# A4a_ESP32-WROOM-32.net
KiCad netlist of a schematic drawn in EAGLE
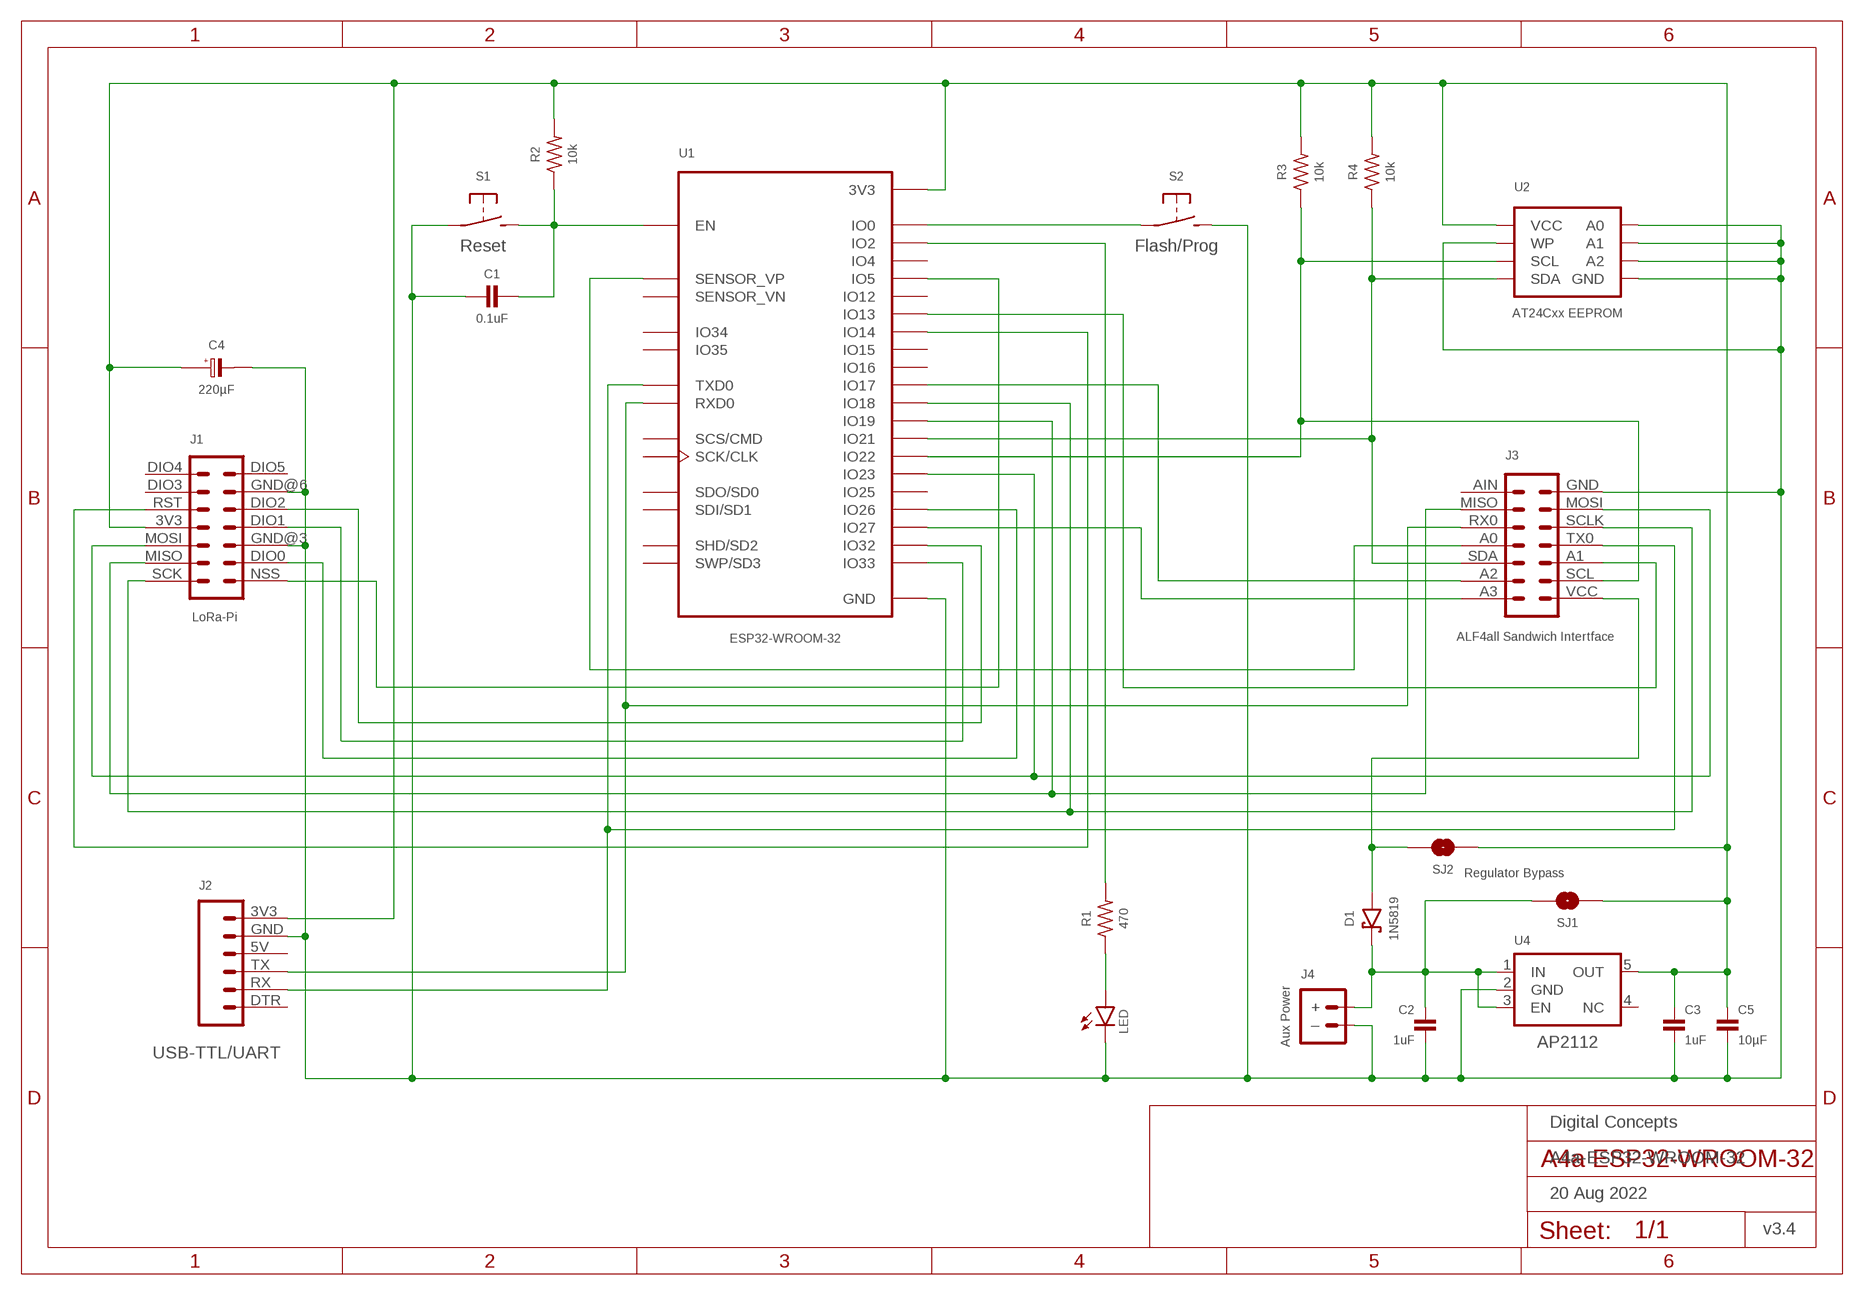
[diagram p0: schematic, sheet 1]

(export (version "E")
  (design (tool "Eeschema 10.0.6"))
  (components
    (comp (ref "C1")
      (value "0.1uF")
      (footprint "eagle-import:C0805@1")
      (libsource (lib "eagle-import") (part "CAPACITOR"))
    )
    (comp (ref "C2")
      (value "1uF")
      (footprint "eagle-import:C0805")
      (libsource (lib "eagle-import") (part "CAPACITOR-0805"))
    )
    (comp (ref "C3")
      (value "1uF")
      (footprint "eagle-import:C0805")
      (libsource (lib "eagle-import") (part "CAPACITOR-0805"))
    )
    (comp (ref "C4")
      (value "220µF")
      (footprint "eagle-import:C3528-21")
      (libsource (lib "eagle-import") (part "CAPACITOR-TANTALUM-3528"))
    )
    (comp (ref "C5")
      (value "10µF")
      (footprint "eagle-import:C0805")
      (libsource (lib "eagle-import") (part "CAPACITOR-0805"))
    )
    (comp (ref "D1")
      (value "1N5819")
      (footprint "eagle-import:SOD-123")
      (libsource (lib "eagle-import") (part "DIODE-SCHOTTKY-1N5819"))
    )
    (comp (ref "J1")
      (value "LoRa-Pi")
      (footprint "eagle-import:RFM95W-PI")
      (libsource (lib "eagle-import") (part "RFM95W-PI-HEADER"))
    )
    (comp (ref "J2")
      (value "USB-TTL/UART")
      (footprint "eagle-import:CONN_06-UART")
      (libsource (lib "eagle-import") (part "HEADER-1X6-UART"))
    )
    (comp (ref "J3")
      (value "ALF4all Sandwich Intertface")
      (footprint "eagle-import:CONN_2X7-ALF4ALL-PROCESSOR-B")
      (libsource (lib "eagle-import") (part "HEADER-2X7-ALF4ALL-PROCESSOR-B"))
    )
    (comp (ref "J4")
      (value "Aux Power")
      (footprint "eagle-import:JST-PH2.0-2-HORIZONTAL")
      (libsource (lib "eagle-import") (part "JST-PH2.0-2-MALE-HORIZONTALJST-PTH-2"))
    )
    (comp (ref "LED")
      (value "LEDCHIP-LED0805")
      (footprint "eagle-import:CHIP-LED0805")
      (libsource (lib "eagle-import") (part "LEDCHIP-LED0805"))
    )
    (comp (ref "R1")
      (value "470")
      (footprint "eagle-import:R0805")
      (libsource (lib "eagle-import") (part "RESISTORR0805"))
    )
    (comp (ref "R2")
      (value "10k")
      (footprint "eagle-import:R0805")
      (libsource (lib "eagle-import") (part "RESISTORR0805"))
    )
    (comp (ref "R3")
      (value "10k")
      (footprint "eagle-import:R0805")
      (libsource (lib "eagle-import") (part "RESISTORR0805"))
    )
    (comp (ref "R4")
      (value "10k")
      (footprint "eagle-import:R0805")
      (libsource (lib "eagle-import") (part "RESISTORR0805"))
    )
    (comp (ref "S1")
      (value "Reset")
      (footprint "eagle-import:SWITCH-2-PAD")
      (libsource (lib "eagle-import") (part "SWITCH-MOMENTARY-2-PIN"))
    )
    (comp (ref "S2")
      (value "Flash/Prog")
      (footprint "eagle-import:SWITCH-2-PAD")
      (libsource (lib "eagle-import") (part "SWITCH-MOMENTARY-2-PIN"))
    )
    (comp (ref "SJ1")
      (value "Regulator Bypass")
      (footprint "eagle-import:SJ")
      (libsource (lib "eagle-import") (part "SJ"))
    )
    (comp (ref "SJ2") (value "SJ") (footprint "eagle-import:SJ") (libsource (lib "eagle-import") (part "SJ")))
    (comp (ref "U1")
      (value "ESP32-WROOM-32")
      (footprint "eagle-import:ESP32-WROOM-32")
      (libsource (lib "eagle-import") (part "ESP32-WROOM-32"))
    )
    (comp (ref "U2")
      (value "AT24Cxx EEPROM")
      (footprint "eagle-import:SOP-8")
      (libsource (lib "eagle-import") (part "AT24CXX-EEPROM"))
    )
    (comp (ref "U4")
      (value "AP2112")
      (footprint "eagle-import:SOT25")
      (libsource (lib "eagle-import") (part "REGULATOR-AP2112"))
    )
  )
  (nets
    (net (code "1") (name "Net-(C4-+)") (class "Default")
      (node (ref "C3") (pin "1") (pinfunction "1_1") (pintype "passive"))
      (node (ref "C4") (pin "1") (pinfunction "+_1") (pintype "passive"))
      (node (ref "C5") (pin "1") (pinfunction "1_1") (pintype "passive"))
      (node (ref "J1") (pin "3V3") (pinfunction "11_3V3") (pintype "passive"))
      (node (ref "J2") (pin "3V3") (pinfunction "6_3V3") (pintype "passive"))
      (node (ref "R2") (pin "2") (pinfunction "2_2") (pintype "passive"))
      (node (ref "R3") (pin "2") (pinfunction "2_2") (pintype "passive"))
      (node (ref "R4") (pin "2") (pinfunction "2_2") (pintype "passive"))
      (node (ref "SJ1") (pin "2") (pinfunction "2_2") (pintype "passive"))
      (node (ref "SJ2") (pin "2") (pinfunction "2_2") (pintype "passive"))
      (node (ref "U1") (pin "3V3") (pinfunction "3V3_3V3") (pintype "power_in"))
      (node (ref "U2") (pin "P$8") (pinfunction "VCC_P$8") (pintype "bidirectional"))
      (node (ref "U4") (pin "5") (pinfunction "OUT_5") (pintype "power_in"))
    )
    (net (code "2") (name "Net-(C4--)") (class "Default")
      (node (ref "C1") (pin "2") (pinfunction "2_2") (pintype "passive"))
      (node (ref "C2") (pin "2") (pinfunction "2_2") (pintype "passive"))
      (node (ref "C3") (pin "2") (pinfunction "2_2") (pintype "passive"))
      (node (ref "C4") (pin "2") (pinfunction "-_2") (pintype "passive"))
      (node (ref "C5") (pin "2") (pinfunction "2_2") (pintype "passive"))
      (node (ref "J1") (pin "GND@3") (pinfunction "3_GND@3") (pintype "passive"))
      (node (ref "J1") (pin "GND@6") (pinfunction "6_GND@6") (pintype "passive"))
      (node (ref "J2") (pin "GND") (pinfunction "5_GND") (pintype "passive"))
      (node (ref "J3") (pin "GND") (pinfunction "7_GND") (pintype "passive"))
      (node (ref "J4") (pin "-") (pinfunction "–_-") (pintype "power_in"))
      (node (ref "LED") (pin "C") (pinfunction "C_C") (pintype "passive"))
      (node (ref "S1") (pin "P$1") (pinfunction "P_P$1") (pintype "passive"))
      (node (ref "S2") (pin "P$2") (pinfunction "S_P$2") (pintype "passive"))
      (node (ref "U1") (pin "GND@1") (pinfunction "GND_GND@1") (pintype "power_in"))
      (node (ref "U1") (pin "GND@15") (pinfunction "GND_GND@15") (pintype "power_in"))
      (node (ref "U1") (pin "GND@38") (pinfunction "GND_GND@38") (pintype "power_in"))
      (node (ref "U1") (pin "TP") (pinfunction "GND_TP") (pintype "power_in"))
      (node (ref "U1") (pin "TP@P1") (pinfunction "GND_TP@P1") (pintype "power_in"))
      (node (ref "U1") (pin "TP@P2") (pinfunction "GND_TP@P2") (pintype "power_in"))
      (node (ref "U1") (pin "TP@P3") (pinfunction "GND_TP@P3") (pintype "power_in"))
      (node (ref "U1") (pin "TP@P4") (pinfunction "GND_TP@P4") (pintype "power_in"))
      (node (ref "U1") (pin "TP@P5") (pinfunction "GND_TP@P5") (pintype "power_in"))
      (node (ref "U1") (pin "TP@P6") (pinfunction "GND_TP@P6") (pintype "power_in"))
      (node (ref "U1") (pin "TP@P7") (pinfunction "GND_TP@P7") (pintype "power_in"))
      (node (ref "U1") (pin "TP@P8") (pinfunction "GND_TP@P8") (pintype "power_in"))
      (node (ref "U1") (pin "TP@P9") (pinfunction "GND_TP@P9") (pintype "power_in"))
      (node (ref "U1") (pin "TP@V1") (pinfunction "GND_TP@V1") (pintype "power_in"))
      (node (ref "U1") (pin "TP@V10") (pinfunction "GND_TP@V10") (pintype "power_in"))
      (node (ref "U1") (pin "TP@V11") (pinfunction "GND_TP@V11") (pintype "power_in"))
      (node (ref "U1") (pin "TP@V12") (pinfunction "GND_TP@V12") (pintype "power_in"))
      (node (ref "U1") (pin "TP@V2") (pinfunction "GND_TP@V2") (pintype "power_in"))
      (node (ref "U1") (pin "TP@V3") (pinfunction "GND_TP@V3") (pintype "power_in"))
      (node (ref "U1") (pin "TP@V4") (pinfunction "GND_TP@V4") (pintype "power_in"))
      (node (ref "U1") (pin "TP@V5") (pinfunction "GND_TP@V5") (pintype "power_in"))
      (node (ref "U1") (pin "TP@V6") (pinfunction "GND_TP@V6") (pintype "power_in"))
      (node (ref "U1") (pin "TP@V7") (pinfunction "GND_TP@V7") (pintype "power_in"))
      (node (ref "U1") (pin "TP@V8") (pinfunction "GND_TP@V8") (pintype "power_in"))
      (node (ref "U1") (pin "TP@V9") (pinfunction "GND_TP@V9") (pintype "power_in"))
      (node (ref "U1") (pin "TP@VP5") (pinfunction "GND_TP@VP5") (pintype "power_in"))
      (node (ref "U2") (pin "P$1") (pinfunction "A0_P$1") (pintype "bidirectional"))
      (node (ref "U2") (pin "P$2") (pinfunction "A1_P$2") (pintype "bidirectional"))
      (node (ref "U2") (pin "P$3") (pinfunction "A2_P$3") (pintype "bidirectional"))
      (node (ref "U2") (pin "P$4") (pinfunction "GND_P$4") (pintype "bidirectional"))
      (node (ref "U2") (pin "P$7") (pinfunction "WP_P$7") (pintype "bidirectional"))
      (node (ref "U4") (pin "2") (pinfunction "GND_2") (pintype "power_in"))
    )
    (net (code "3") (name "Net-(J1-1)") (class "Default")
      (node (ref "J1") (pin "NSS") (pinfunction "1_NSS") (pintype "passive"))
      (node (ref "U1") (pin "IO5") (pinfunction "IO5_IO5") (pintype "bidirectional"))
    )
    (net (code "4") (name "Net-(J1-2)") (class "Default")
      (node (ref "J1") (pin "DIO0") (pinfunction "2_DIO0") (pintype "passive"))
      (node (ref "U1") (pin "IO26") (pinfunction "IO26_IO26") (pintype "bidirectional"))
    )
    (net (code "5") (name "Net-(J1-4)") (class "Default")
      (node (ref "J1") (pin "DIO1") (pinfunction "4_DIO1") (pintype "passive"))
      (node (ref "U1") (pin "IO33") (pinfunction "IO33_IO33") (pintype "bidirectional"))
    )
    (net (code "6") (name "Net-(J1-5)") (class "Default")
      (node (ref "J1") (pin "DIO2") (pinfunction "5_DIO2") (pintype "passive"))
      (node (ref "U1") (pin "IO32") (pinfunction "IO32_IO32") (pintype "bidirectional"))
    )
    (net (code "7") (name "Net-(J1-10)") (class "Default")
      (node (ref "J1") (pin "RST") (pinfunction "10_RST") (pintype "passive"))
      (node (ref "U1") (pin "IO14") (pinfunction "IO14_IO14") (pintype "bidirectional"))
    )
    (net (code "8") (name "Net-(J1-12)") (class "Default")
      (node (ref "J1") (pin "MOSI") (pinfunction "12_MOSI") (pintype "passive"))
      (node (ref "J3") (pin "MOSI") (pinfunction "6_MOSI") (pintype "passive"))
      (node (ref "U1") (pin "IO23") (pinfunction "IO23_IO23") (pintype "bidirectional"))
    )
    (net (code "9") (name "Net-(J1-13)") (class "Default")
      (node (ref "J1") (pin "MISO") (pinfunction "13_MISO") (pintype "passive"))
      (node (ref "J3") (pin "MISO") (pinfunction "9_MISO") (pintype "passive"))
      (node (ref "U1") (pin "IO19") (pinfunction "IO19_IO19") (pintype "bidirectional"))
    )
    (net (code "10") (name "Net-(J1-14)") (class "Default")
      (node (ref "J1") (pin "SCK") (pinfunction "14_SCK") (pintype "passive"))
      (node (ref "J3") (pin "SCLK") (pinfunction "5_SCLK") (pintype "passive"))
      (node (ref "U1") (pin "IO18") (pinfunction "IO18_IO18") (pintype "bidirectional"))
    )
    (net (code "11") (name "Net-(J2-2)") (class "Default")
      (node (ref "J2") (pin "RX") (pinfunction "2_RX") (pintype "passive"))
      (node (ref "J3") (pin "TX0") (pinfunction "4_TX0") (pintype "passive"))
      (node (ref "U1") (pin "TXD0") (pinfunction "TXD0_TXD0") (pintype "bidirectional"))
    )
    (net (code "12") (name "Net-(J2-3)") (class "Default")
      (node (ref "J2") (pin "TX") (pinfunction "3_TX") (pintype "passive"))
      (node (ref "J3") (pin "RX0") (pinfunction "10_RX0") (pintype "passive"))
      (node (ref "U1") (pin "RXD0") (pinfunction "RXD0_RXD0") (pintype "bidirectional"))
    )
    (net (code "13") (name "Net-(J3-1)") (class "Default")
      (node (ref "D1") (pin "A") (pinfunction "A_A") (pintype "passive"))
      (node (ref "J3") (pin "VCC") (pinfunction "1_VCC") (pintype "passive"))
      (node (ref "SJ2") (pin "1") (pinfunction "1_1") (pintype "passive"))
    )
    (net (code "14") (name "Net-(J3-2)") (class "Default")
      (node (ref "J3") (pin "SCL") (pinfunction "2_SCL") (pintype "passive"))
      (node (ref "R3") (pin "1") (pinfunction "1_1") (pintype "passive"))
      (node (ref "U1") (pin "IO22") (pinfunction "IO22_IO22") (pintype "bidirectional"))
      (node (ref "U2") (pin "P$6") (pinfunction "SCL_P$6") (pintype "bidirectional"))
    )
    (net (code "15") (name "Net-(J3-3)") (class "Default")
      (node (ref "J3") (pin "A1") (pinfunction "3_A1") (pintype "passive"))
      (node (ref "U1") (pin "IO13") (pinfunction "IO13_IO13") (pintype "bidirectional"))
    )
    (net (code "16") (name "Net-(J3-11)") (class "Default")
      (node (ref "J3") (pin "A0") (pinfunction "11_A0") (pintype "passive"))
      (node (ref "U1") (pin "SENSOR_VP") (pinfunction "SENSOR_VP_SENSOR_VP") (pintype "input"))
    )
    (net (code "17") (name "Net-(J3-12)") (class "Default")
      (node (ref "J3") (pin "SDA") (pinfunction "12_SDA") (pintype "passive"))
      (node (ref "R4") (pin "1") (pinfunction "1_1") (pintype "passive"))
      (node (ref "U1") (pin "IO21") (pinfunction "IO21_IO21") (pintype "bidirectional"))
      (node (ref "U2") (pin "P$5") (pinfunction "SDA_P$5") (pintype "bidirectional"))
    )
    (net (code "18") (name "Net-(J3-13)") (class "Default")
      (node (ref "J3") (pin "A2") (pinfunction "13_A2") (pintype "passive"))
      (node (ref "U1") (pin "IO17") (pinfunction "IO17_IO17") (pintype "bidirectional"))
    )
    (net (code "19") (name "Net-(J3-14)") (class "Default")
      (node (ref "J3") (pin "A3") (pinfunction "14_A3") (pintype "passive"))
      (node (ref "U1") (pin "IO27") (pinfunction "IO27_IO27") (pintype "bidirectional"))
    )
    (net (code "20") (name "Net-(LED-PadA)") (class "Default")
      (node (ref "LED") (pin "A") (pinfunction "A_A") (pintype "passive"))
      (node (ref "R1") (pin "1") (pinfunction "1_1") (pintype "passive"))
    )
    (net (code "21") (name "Net-(R1-Pad2)") (class "Default")
      (node (ref "R1") (pin "2") (pinfunction "2_2") (pintype "passive"))
      (node (ref "U1") (pin "IO2") (pinfunction "IO2_IO2") (pintype "bidirectional"))
    )
    (net (code "22") (name "Net-(S1-S)") (class "Default")
      (node (ref "C1") (pin "1") (pinfunction "1_1") (pintype "passive"))
      (node (ref "R2") (pin "1") (pinfunction "1_1") (pintype "passive"))
      (node (ref "S1") (pin "P$2") (pinfunction "S_P$2") (pintype "passive"))
      (node (ref "U1") (pin "EN") (pinfunction "EN_EN") (pintype "input"))
    )
    (net (code "23") (name "Net-(S2-P)") (class "Default")
      (node (ref "S2") (pin "P$1") (pinfunction "P_P$1") (pintype "passive"))
      (node (ref "U1") (pin "IO0") (pinfunction "IO0_IO0") (pintype "bidirectional"))
    )
    (net (code "24") (name "Net-(U4-EN)") (class "Default")
      (node (ref "C2") (pin "1") (pinfunction "1_1") (pintype "passive"))
      (node (ref "D1") (pin "C") (pinfunction "C_C") (pintype "passive"))
      (node (ref "J4") (pin "+") (pinfunction "+_+") (pintype "power_in"))
      (node (ref "SJ1") (pin "1") (pinfunction "1_1") (pintype "passive"))
      (node (ref "U4") (pin "1") (pinfunction "IN_1") (pintype "power_in"))
      (node (ref "U4") (pin "3") (pinfunction "EN_3") (pintype "input"))
    )
    (net (code "25") (name "unconnected-(J1-7-PadDIO5)") (class "Default")
      (node (ref "J1") (pin "DIO5") (pinfunction "7_DIO5") (pintype "passive"))
    )
    (net (code "26") (name "unconnected-(J1-8-PadDIO4)") (class "Default")
      (node (ref "J1") (pin "DIO4") (pinfunction "8_DIO4") (pintype "passive"))
    )
    (net (code "27") (name "unconnected-(J1-9-PadDIO3)") (class "Default")
      (node (ref "J1") (pin "DIO3") (pinfunction "9_DIO3") (pintype "passive"))
    )
    (net (code "28") (name "unconnected-(J2-1-PadDTR)") (class "Default")
      (node (ref "J2") (pin "DTR") (pinfunction "1_DTR") (pintype "passive"))
    )
    (net (code "29") (name "unconnected-(J2-4-Pad5V)") (class "Default")
      (node (ref "J2") (pin "5V") (pinfunction "4_5V") (pintype "passive"))
    )
    (net (code "30") (name "unconnected-(J3-8-PadAIN)") (class "Default")
      (node (ref "J3") (pin "AIN") (pinfunction "8_AIN") (pintype "passive"))
    )
    (net (code "31") (name "unconnected-(U1-PadIO4)") (class "Default")
      (node (ref "U1") (pin "IO4") (pinfunction "IO4_IO4") (pintype "bidirectional"))
    )
    (net (code "32") (name "unconnected-(U1-PadIO12)") (class "Default")
      (node (ref "U1") (pin "IO12") (pinfunction "IO12_IO12") (pintype "bidirectional"))
    )
    (net (code "33") (name "unconnected-(U1-PadIO15)") (class "Default")
      (node (ref "U1") (pin "IO15") (pinfunction "IO15_IO15") (pintype "bidirectional"))
    )
    (net (code "34") (name "unconnected-(U1-PadIO16)") (class "Default")
      (node (ref "U1") (pin "IO16") (pinfunction "IO16_IO16") (pintype "bidirectional"))
    )
    (net (code "35") (name "unconnected-(U1-PadIO25)") (class "Default")
      (node (ref "U1") (pin "IO25") (pinfunction "IO25_IO25") (pintype "bidirectional"))
    )
    (net (code "36") (name "unconnected-(U1-PadIO34)") (class "Default")
      (node (ref "U1") (pin "IO34") (pinfunction "IO34_IO34") (pintype "input"))
    )
    (net (code "37") (name "unconnected-(U1-PadIO35)") (class "Default")
      (node (ref "U1") (pin "IO35") (pinfunction "IO35_IO35") (pintype "input"))
    )
    (net (code "38") (name "unconnected-(U1-PadSENSOR_VN)") (class "Default")
      (node (ref "U1") (pin "SENSOR_VN") (pinfunction "SENSOR_VN_SENSOR_VN") (pintype "input"))
    )
    (net (code "39") (name "unconnected-(U1-SCK{slash}CLK-PadCLK)") (class "Default")
      (node (ref "U1") (pin "CLK") (pinfunction "SCK/CLK_CLK") (pintype "bidirectional"))
    )
    (net (code "40") (name "unconnected-(U1-SCS{slash}CMD-PadCMD)") (class "Default")
      (node (ref "U1") (pin "CMD") (pinfunction "SCS/CMD_CMD") (pintype "bidirectional"))
    )
    (net (code "41") (name "unconnected-(U1-SDI{slash}SD1-PadSD1)") (class "Default")
      (node (ref "U1") (pin "SD1") (pinfunction "SDI/SD1_SD1") (pintype "bidirectional"))
    )
    (net (code "42") (name "unconnected-(U1-SDO{slash}SD0-PadSD0)") (class "Default")
      (node (ref "U1") (pin "SD0") (pinfunction "SDO/SD0_SD0") (pintype "bidirectional"))
    )
    (net (code "43") (name "unconnected-(U1-SHD{slash}SD2-PadSD2)") (class "Default")
      (node (ref "U1") (pin "SD2") (pinfunction "SHD/SD2_SD2") (pintype "bidirectional"))
    )
    (net (code "44") (name "unconnected-(U1-SWP{slash}SD3-PadSD3)") (class "Default")
      (node (ref "U1") (pin "SD3") (pinfunction "SWP/SD3_SD3") (pintype "bidirectional"))
    )
    (net (code "45") (name "unconnected-(U4-NC-Pad4)") (class "Default")
      (node (ref "U4") (pin "4") (pinfunction "NC_4") (pintype "no_connect"))
    )
  )
)
